# Adafruit_ATtiny816_Breakout.net
KiCad netlist of a schematic drawn in EAGLE
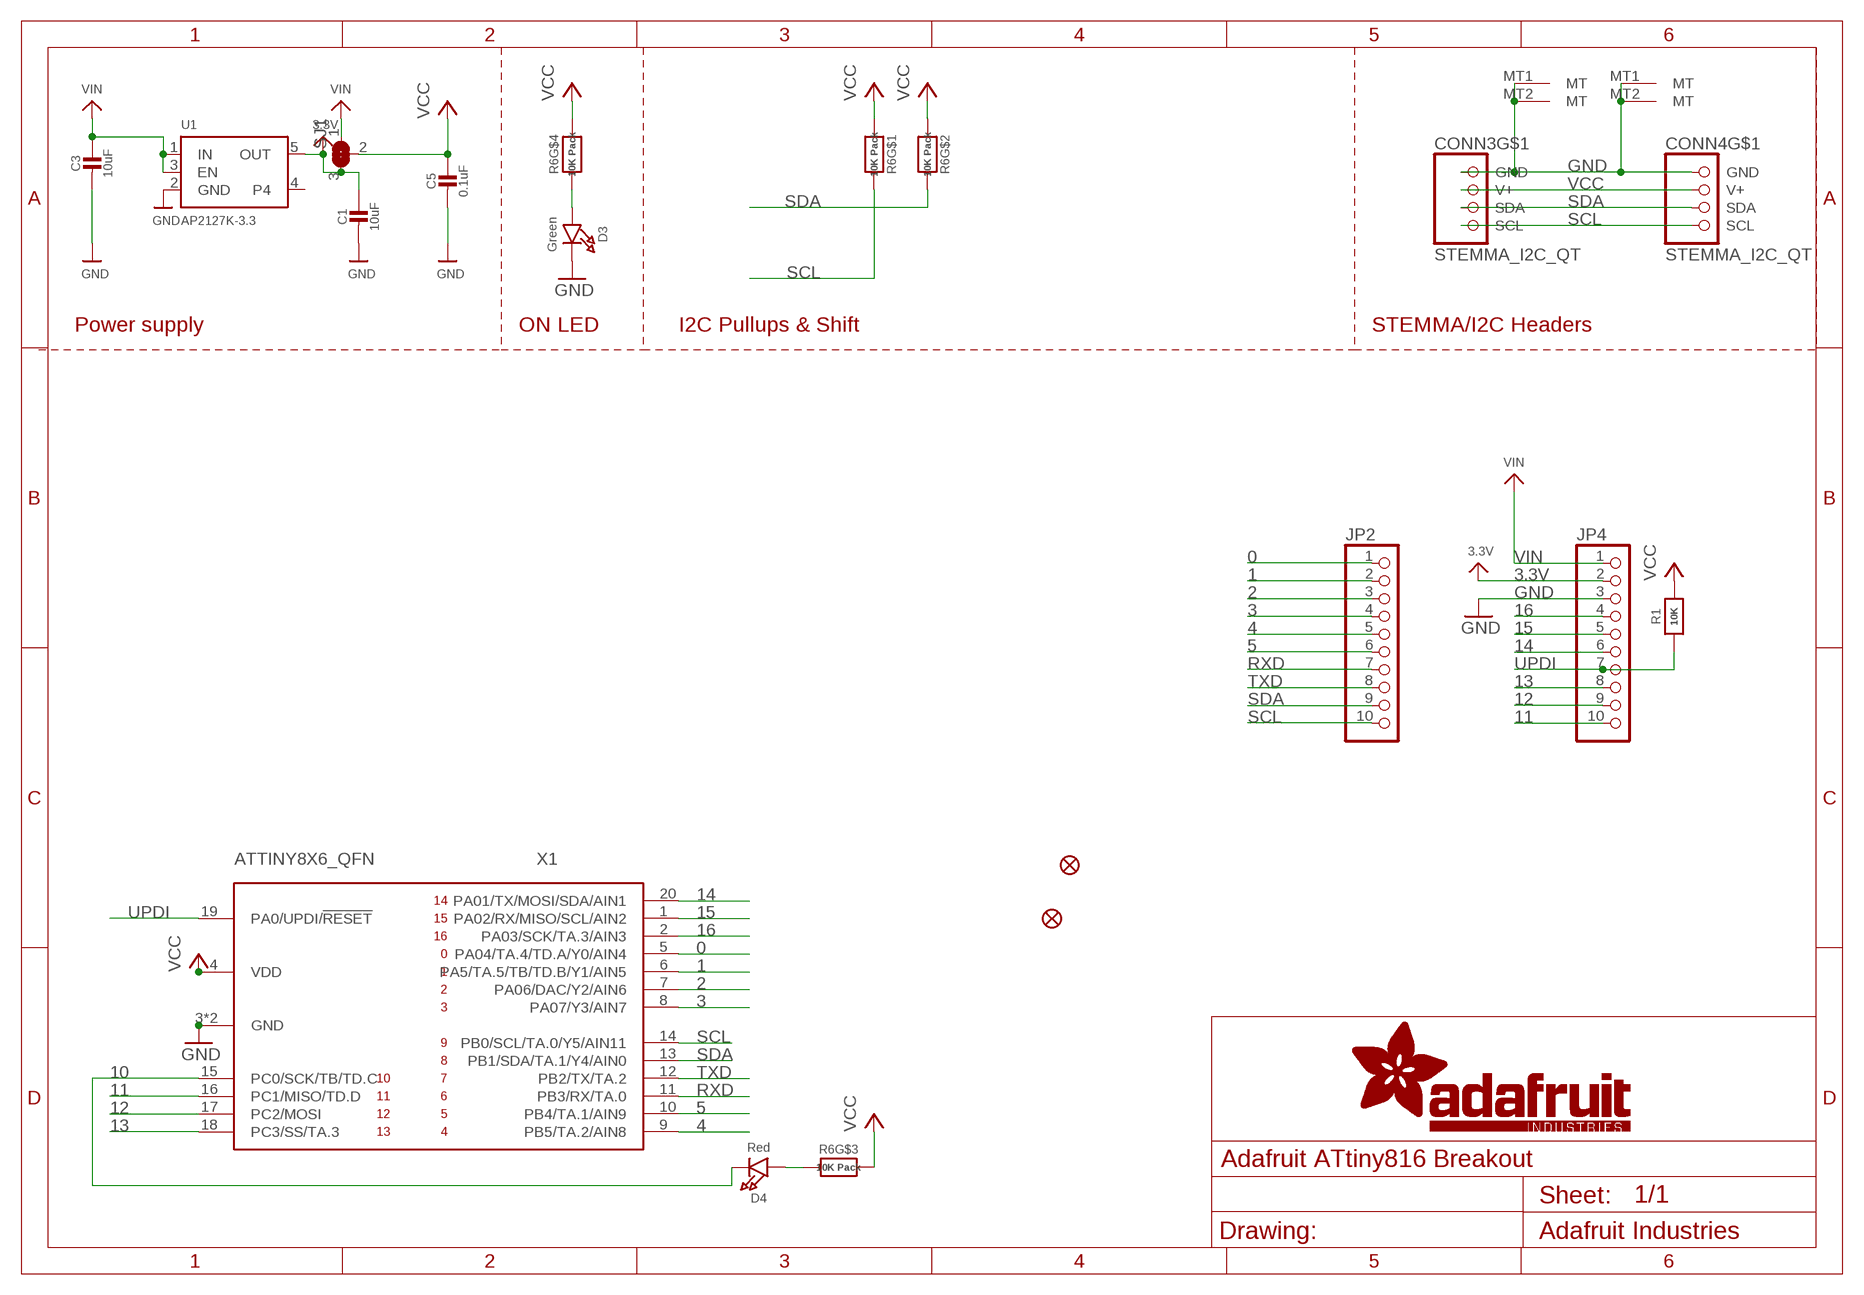
[diagram p0: schematic, sheet 1]

(export (version "E")
  (design (tool "Eeschema 10.0.6"))
  (components
    (comp (ref "C1")
      (value "10uF")
      (footprint "eagle-import:0805_10MGAP")
      (libsource (lib "eagle-import") (part "CAP_CERAMIC0805_10MGAP"))
    )
    (comp (ref "C3")
      (value "10uF")
      (footprint "eagle-import:0805-NO")
      (libsource (lib "eagle-import") (part "CAP_CERAMIC0805-NOOUTLINE"))
    )
    (comp (ref "C5")
      (value "0.1uF")
      (footprint "eagle-import:0603-NO")
      (libsource (lib "eagle-import") (part "CAP_CERAMIC0603_NO"))
    )
    (comp (ref "CONN3")
      (value "STEMMA_I2C_QT")
      (footprint "eagle-import:JST_SH4")
      (libsource (lib "eagle-import") (part "STEMMA_I2C_QT"))
    )
    (comp (ref "CONN4")
      (value "STEMMA_I2C_QT")
      (footprint "eagle-import:JST_SH4")
      (libsource (lib "eagle-import") (part "STEMMA_I2C_QT"))
    )
    (comp (ref "D3")
      (value "Green")
      (footprint "eagle-import:CHIPLED_0603_NOOUTLINE")
      (libsource (lib "eagle-import") (part "LED0603_NOOUTLINE"))
    )
    (comp (ref "D4")
      (value "Red")
      (footprint "eagle-import:CHIPLED_0603_NOOUTLINE")
      (libsource (lib "eagle-import") (part "LED0603_NOOUTLINE"))
    )
    (comp (ref "FID1")
      (value "FIDUCIAL_1MM")
      (footprint "eagle-import:FIDUCIAL_1MM")
      (libsource (lib "eagle-import") (part "FIDUCIAL_1MM"))
    )
    (comp (ref "FID2")
      (value "FIDUCIAL_1MM")
      (footprint "eagle-import:FIDUCIAL_1MM")
      (libsource (lib "eagle-import") (part "FIDUCIAL_1MM"))
    )
    (comp (ref "JP2")
      (value "HEADER-1X1070MIL")
      (footprint "eagle-import:1X10_ROUND70")
      (libsource (lib "eagle-import") (part "HEADER-1X1070MIL"))
    )
    (comp (ref "JP4")
      (value "HEADER-1X1070MIL")
      (footprint "eagle-import:1X10_ROUND70")
      (libsource (lib "eagle-import") (part "HEADER-1X1070MIL"))
    )
    (comp (ref "R1")
      (value "10K")
      (footprint "eagle-import:0603-NO")
      (libsource (lib "eagle-import") (part "RESISTOR_0603_NOOUT"))
    )
    (comp (ref "R6")
      (value "10K Pack")
      (footprint "eagle-import:RESPACK_4X0603")
      (libsource (lib "eagle-import") (part "RESISTOR_4PACK"))
    )
    (comp (ref "SJ1")
      (value "SOLDERJUMPER_2WAY")
      (footprint "eagle-import:SOLDERJUMPER_2WAY_OPEN_NOPASTE")
      (libsource (lib "eagle-import") (part "SOLDERJUMPER_2WAY"))
    )
    (comp (ref "U1")
      (value "AP2127K-3.3")
      (footprint "eagle-import:SOT23-5")
      (libsource (lib "eagle-import") (part "VREG_SOT23-5"))
    )
    (comp (ref "X1")
      (value "ATTINY8X6_QFN")
      (footprint "eagle-import:QFN20_3MM")
      (libsource (lib "eagle-import") (part "ATTINY8X6_QFN"))
    )
  )
  (nets
    (net (code "1") (name "/0") (class "Default")
      (node (ref "JP2") (pin "1") (pinfunction "1_1") (pintype "passive"))
      (node (ref "X1") (pin "5") (pinfunction "PA04/TA.4/TD.A/Y0/AIN4_5") (pintype "bidirectional"))
    )
    (net (code "2") (name "/1") (class "Default")
      (node (ref "JP2") (pin "2") (pinfunction "2_2") (pintype "passive"))
      (node (ref "X1") (pin "6") (pinfunction "PA5/TA.5/TB/TD.B/Y1/AIN5_6") (pintype "bidirectional"))
    )
    (net (code "3") (name "/2") (class "Default")
      (node (ref "JP2") (pin "3") (pinfunction "3_3") (pintype "passive"))
      (node (ref "X1") (pin "7") (pinfunction "PA06/DAC/Y2/AIN6_7") (pintype "bidirectional"))
    )
    (net (code "4") (name "/3") (class "Default")
      (node (ref "JP2") (pin "4") (pinfunction "4_4") (pintype "passive"))
      (node (ref "X1") (pin "8") (pinfunction "PA07/Y3/AIN7_8") (pintype "bidirectional"))
    )
    (net (code "5") (name "/4") (class "Default")
      (node (ref "JP2") (pin "5") (pinfunction "5_5") (pintype "passive"))
      (node (ref "X1") (pin "9") (pinfunction "PB5/TA.2/AIN8_9") (pintype "bidirectional"))
    )
    (net (code "6") (name "/5") (class "Default")
      (node (ref "JP2") (pin "6") (pinfunction "6_6") (pintype "passive"))
      (node (ref "X1") (pin "10") (pinfunction "PB4/TA.1/AIN9_10") (pintype "bidirectional"))
    )
    (net (code "7") (name "/10") (class "Default")
      (node (ref "D4") (pin "C") (pinfunction "C_C") (pintype "passive"))
      (node (ref "X1") (pin "15") (pinfunction "PC0/SCK/TB/TD.C_15") (pintype "bidirectional"))
    )
    (net (code "8") (name "/11") (class "Default")
      (node (ref "JP4") (pin "10") (pinfunction "10_10") (pintype "passive"))
      (node (ref "X1") (pin "16") (pinfunction "PC1/MISO/TD.D_16") (pintype "bidirectional"))
    )
    (net (code "9") (name "/12") (class "Default")
      (node (ref "JP4") (pin "9") (pinfunction "9_9") (pintype "passive"))
      (node (ref "X1") (pin "17") (pinfunction "PC2/MOSI_17") (pintype "bidirectional"))
    )
    (net (code "10") (name "/13") (class "Default")
      (node (ref "JP4") (pin "8") (pinfunction "8_8") (pintype "passive"))
      (node (ref "X1") (pin "18") (pinfunction "PC3/SS/TA.3_18") (pintype "bidirectional"))
    )
    (net (code "11") (name "/14") (class "Default")
      (node (ref "JP4") (pin "6") (pinfunction "6_6") (pintype "passive"))
      (node (ref "X1") (pin "20") (pinfunction "PA01/TX/MOSI/SDA/AIN1_20") (pintype "bidirectional"))
    )
    (net (code "12") (name "/15") (class "Default")
      (node (ref "JP4") (pin "5") (pinfunction "5_5") (pintype "passive"))
      (node (ref "X1") (pin "1") (pinfunction "PA02/RX/MISO/SCL/AIN2_1") (pintype "bidirectional"))
    )
    (net (code "13") (name "/16") (class "Default")
      (node (ref "JP4") (pin "4") (pinfunction "4_4") (pintype "passive"))
      (node (ref "X1") (pin "2") (pinfunction "PA03/SCK/TA.3/AIN3_2") (pintype "bidirectional"))
    )
    (net (code "14") (name "/RXD") (class "Default")
      (node (ref "JP2") (pin "7") (pinfunction "7_7") (pintype "passive"))
      (node (ref "X1") (pin "11") (pinfunction "PB3/RX/TA.0_11") (pintype "bidirectional"))
    )
    (net (code "15") (name "/SCL") (class "Default")
      (node (ref "CONN3") (pin "4") (pinfunction "SCL_4") (pintype "passive"))
      (node (ref "CONN4") (pin "4") (pinfunction "SCL_4") (pintype "passive"))
      (node (ref "JP2") (pin "10") (pinfunction "10_10") (pintype "passive"))
      (node (ref "R6") (pin "8") (pinfunction "2_8") (pintype "passive"))
      (node (ref "X1") (pin "14") (pinfunction "PB0/SCL/TA.0/Y5/AIN11_14") (pintype "bidirectional"))
    )
    (net (code "16") (name "/SDA") (class "Default")
      (node (ref "CONN3") (pin "3") (pinfunction "SDA_3") (pintype "passive"))
      (node (ref "CONN4") (pin "3") (pinfunction "SDA_3") (pintype "passive"))
      (node (ref "JP2") (pin "9") (pinfunction "9_9") (pintype "passive"))
      (node (ref "R6") (pin "7") (pinfunction "2_7") (pintype "passive"))
      (node (ref "X1") (pin "13") (pinfunction "PB1/SDA/TA.1/Y4/AIN0_13") (pintype "bidirectional"))
    )
    (net (code "17") (name "/TXD") (class "Default")
      (node (ref "JP2") (pin "8") (pinfunction "8_8") (pintype "passive"))
      (node (ref "X1") (pin "12") (pinfunction "PB2/TX/TA.2_12") (pintype "bidirectional"))
    )
    (net (code "18") (name "/UPDI") (class "Default")
      (node (ref "JP4") (pin "7") (pinfunction "7_7") (pintype "passive"))
      (node (ref "R1") (pin "1") (pinfunction "1_1") (pintype "passive"))
      (node (ref "X1") (pin "19") (pinfunction "PA0/UPDI/~{RESET}_19") (pintype "bidirectional"))
    )
    (net (code "19") (name "3.3V") (class "Default")
      (node (ref "C1") (pin "1") (pinfunction "1_1") (pintype "passive"))
      (node (ref "JP4") (pin "2") (pinfunction "2_2") (pintype "passive"))
      (node (ref "SJ1") (pin "3") (pinfunction "3_3") (pintype "passive"))
      (node (ref "U1") (pin "5") (pinfunction "OUT_5") (pintype "power_in"))
    )
    (net (code "20") (name "GND") (class "Default")
      (node (ref "C1") (pin "2") (pinfunction "2_2") (pintype "passive"))
      (node (ref "C3") (pin "2") (pinfunction "2_2") (pintype "passive"))
      (node (ref "C5") (pin "2") (pinfunction "2_2") (pintype "passive"))
      (node (ref "CONN3") (pin "1") (pinfunction "GND_1") (pintype "passive"))
      (node (ref "CONN3") (pin "MT1") (pinfunction "MT_MT1") (pintype "bidirectional"))
      (node (ref "CONN3") (pin "MT2") (pinfunction "MT_MT2") (pintype "bidirectional"))
      (node (ref "CONN4") (pin "1") (pinfunction "GND_1") (pintype "passive"))
      (node (ref "CONN4") (pin "MT1") (pinfunction "MT_MT1") (pintype "bidirectional"))
      (node (ref "CONN4") (pin "MT2") (pinfunction "MT_MT2") (pintype "bidirectional"))
      (node (ref "D3") (pin "C") (pinfunction "C_C") (pintype "passive"))
      (node (ref "JP4") (pin "3") (pinfunction "3_3") (pintype "passive"))
      (node (ref "U1") (pin "2") (pinfunction "GND_2") (pintype "power_in"))
      (node (ref "X1") (pin "3") (pinfunction "GND_3") (pintype "power_in"))
      (node (ref "X1") (pin "PAD") (pinfunction "GND_PAD") (pintype "power_in"))
    )
    (net (code "21") (name "Net-(R6C-1)") (class "Default")
      (node (ref "D4") (pin "A") (pinfunction "A_A") (pintype "passive"))
      (node (ref "R6") (pin "3") (pinfunction "1_3") (pintype "passive"))
    )
    (net (code "22") (name "Net-(R6D-1)") (class "Default")
      (node (ref "D3") (pin "A") (pinfunction "A_A") (pintype "passive"))
      (node (ref "R6") (pin "4") (pinfunction "1_4") (pintype "passive"))
    )
    (net (code "23") (name "VCC") (class "Default")
      (node (ref "C5") (pin "1") (pinfunction "1_1") (pintype "passive"))
      (node (ref "CONN3") (pin "2") (pinfunction "V+_2") (pintype "passive"))
      (node (ref "CONN4") (pin "2") (pinfunction "V+_2") (pintype "passive"))
      (node (ref "R1") (pin "2") (pinfunction "2_2") (pintype "passive"))
      (node (ref "R6") (pin "1") (pinfunction "1_1") (pintype "passive"))
      (node (ref "R6") (pin "2") (pinfunction "1_2") (pintype "passive"))
      (node (ref "R6") (pin "5") (pinfunction "2_5") (pintype "passive"))
      (node (ref "R6") (pin "6") (pinfunction "2_6") (pintype "passive"))
      (node (ref "SJ1") (pin "2") (pinfunction "2_2") (pintype "passive"))
      (node (ref "X1") (pin "4") (pinfunction "VDD_4") (pintype "power_in"))
    )
    (net (code "24") (name "VIN") (class "Default")
      (node (ref "C3") (pin "1") (pinfunction "1_1") (pintype "passive"))
      (node (ref "JP4") (pin "1") (pinfunction "1_1") (pintype "passive"))
      (node (ref "SJ1") (pin "1") (pinfunction "1_1") (pintype "passive"))
      (node (ref "U1") (pin "1") (pinfunction "IN_1") (pintype "power_in"))
      (node (ref "U1") (pin "3") (pinfunction "EN_3") (pintype "input"))
    )
    (net (code "25") (name "unconnected-(U1-P4-Pad4)") (class "Default")
      (node (ref "U1") (pin "4") (pinfunction "P4_4") (pintype "bidirectional"))
    )
  )
)
